# IMU.net
KiCad netlist of a schematic drawn in Altium Designer
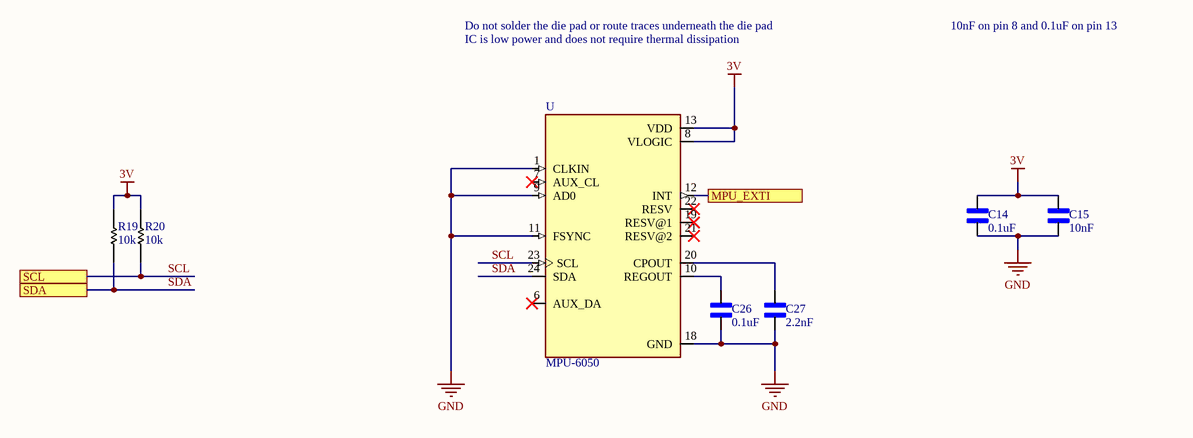
[diagram p0: IMU.SchDoc]

(export (version "E")
  (design (tool "Eeschema 10.0.6"))
  (components
    (comp (ref "C14")
      (value "0.1uF")
      (footprint "0402 Capacitor Generic")
      (description "Generic 0402 Ceramic Capacitor")
      (fields (field (name "MP") "AC0402FR-071ML") (field (name "MF") "Yageo"))
      (libsource (lib "Brushed_Quadcopter_FC_lib") (part "0402 Ceramic Capacitor"))
    )
    (comp (ref "C15")
      (value "10nF")
      (footprint "0402 Capacitor Generic")
      (description "Generic 0402 Ceramic Capacitor")
      (fields (field (name "MP") "AC0402FR-071ML") (field (name "MF") "Yageo"))
      (libsource (lib "Brushed_Quadcopter_FC_lib") (part "0402 Ceramic Capacitor"))
    )
    (comp (ref "C26")
      (value "0.1uF")
      (footprint "0402 Capacitor Generic")
      (description "Generic 0402 Ceramic Capacitor")
      (fields (field (name "MP") "AC0402FR-071ML") (field (name "MF") "Yageo"))
      (libsource (lib "Brushed_Quadcopter_FC_lib") (part "0402 Ceramic Capacitor"))
    )
    (comp (ref "C27")
      (value "2.2nF")
      (footprint "0402 Capacitor Generic")
      (description "Generic 0402 Ceramic Capacitor")
      (fields (field (name "MP") "AC0402FR-071ML") (field (name "MF") "Yageo"))
      (libsource (lib "Brushed_Quadcopter_FC_lib") (part "0402 Ceramic Capacitor"))
    )
    (comp (ref "R19")
      (value "10k")
      (footprint "0402 Resistor Generic")
      (description "Generic 0402 Resistor")
      (libsource (lib "Brushed_Quadcopter_FC_lib") (part "0402 Generic Resistor"))
    )
    (comp (ref "R20")
      (value "10k")
      (footprint "0402 Resistor Generic")
      (description "Generic 0402 Resistor")
      (libsource (lib "Brushed_Quadcopter_FC_lib") (part "0402 Generic Resistor"))
    )
    (comp (ref "U")
      (value "MPU-6050")
      (footprint "MPU-6050")
      (description "Accelerometer, Gyroscope, 6 Axis Sensor IÂ²C Output")
      (fields (field (name "MF") "TDK InvenSense"))
      (libsource (lib "Brushed_Quadcopter_FC_lib") (part "MPU-6050"))
    )
  )
  (nets
    (net (code "1") (name "/MPU_EXTI") (class "Default")
      (node (ref "U") (pin "12") (pinfunction "INT_12") (pintype "output"))
    )
    (net (code "2") (name "/SCL") (class "Default")
      (node (ref "R20") (pin "2") (pinfunction "2_2") (pintype "passive"))
      (node (ref "U") (pin "23") (pinfunction "SCL_23") (pintype "input"))
    )
    (net (code "3") (name "/SDA") (class "Default")
      (node (ref "R19") (pin "2") (pinfunction "2_2") (pintype "passive"))
      (node (ref "U") (pin "24") (pinfunction "SDA_24") (pintype "bidirectional"))
    )
    (net (code "4") (name "3V") (class "Default")
      (node (ref "C14") (pin "1") (pinfunction "1_1") (pintype "passive"))
      (node (ref "C15") (pin "1") (pinfunction "1_1") (pintype "passive"))
      (node (ref "R19") (pin "1") (pinfunction "1_1") (pintype "passive"))
      (node (ref "R20") (pin "1") (pinfunction "1_1") (pintype "passive"))
      (node (ref "U") (pin "13") (pinfunction "VDD_13") (pintype "power_in"))
      (node (ref "U") (pin "8") (pinfunction "VLOGIC_8") (pintype "power_in"))
    )
    (net (code "5") (name "GND") (class "Default")
      (node (ref "C14") (pin "2") (pinfunction "2_2") (pintype "passive"))
      (node (ref "C15") (pin "2") (pinfunction "2_2") (pintype "passive"))
      (node (ref "C26") (pin "2") (pinfunction "2_2") (pintype "passive"))
      (node (ref "C27") (pin "2") (pinfunction "2_2") (pintype "passive"))
      (node (ref "U") (pin "1") (pinfunction "CLKIN_1") (pintype "input"))
      (node (ref "U") (pin "11") (pinfunction "FSYNC_11") (pintype "input"))
      (node (ref "U") (pin "18") (pinfunction "GND_18") (pintype "power_in"))
      (node (ref "U") (pin "9") (pinfunction "AD0_9") (pintype "input"))
    )
    (net (code "6") (name "Net-(U-CPOUT)") (class "Default")
      (node (ref "C27") (pin "1") (pinfunction "1_1") (pintype "passive"))
      (node (ref "U") (pin "20") (pinfunction "CPOUT_20") (pintype "passive"))
    )
    (net (code "7") (name "Net-(U-REGOUT)") (class "Default")
      (node (ref "C26") (pin "1") (pinfunction "1_1") (pintype "passive"))
      (node (ref "U") (pin "10") (pinfunction "REGOUT_10") (pintype "passive"))
    )
    (net (code "8") (name "unconnected-(U-AUX_CL-Pad7)") (class "Default")
      (node (ref "U") (pin "7") (pinfunction "AUX_CL_7") (pintype "input+no_connect"))
    )
    (net (code "9") (name "unconnected-(U-AUX_DA-Pad6)") (class "Default")
      (node (ref "U") (pin "6") (pinfunction "AUX_DA_6") (pintype "bidirectional+no_connect"))
    )
    (net (code "10") (name "unconnected-(U-RESV-Pad22)") (class "Default")
      (node (ref "U") (pin "22") (pinfunction "RESV_22") (pintype "passive+no_connect"))
    )
    (net (code "11") (name "unconnected-(U-RESV@1-Pad19)") (class "Default")
      (node (ref "U") (pin "19") (pinfunction "RESV@1_19") (pintype "passive+no_connect"))
    )
    (net (code "12") (name "unconnected-(U-RESV@2-Pad21)") (class "Default")
      (node (ref "U") (pin "21") (pinfunction "RESV@2_21") (pintype "passive+no_connect"))
    )
  )
)
